# Stylophone.net
KiCad netlist of a schematic drawn in Altium Designer
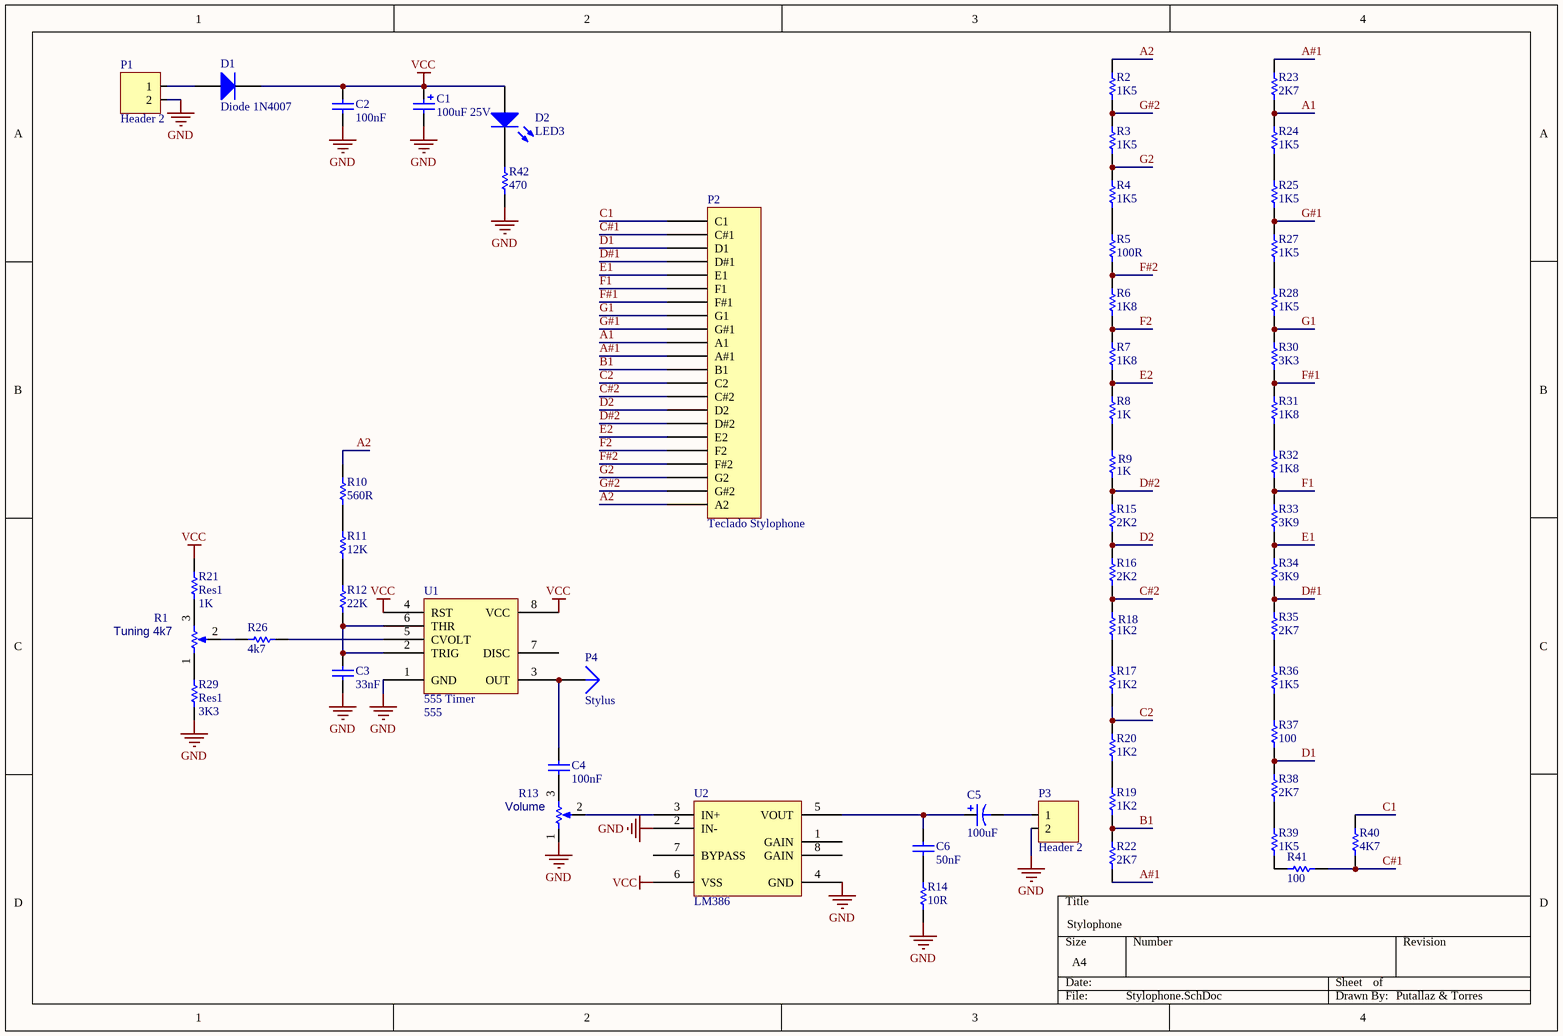
[diagram p0: Stylophone.SchDoc]

(export (version "E")
  (design (tool "Eeschema 10.0.6"))
  (components
    (comp (ref "C1")
      (value "100uF 25V")
      (footprint "CAP SMD 100uF 25V")
      (description "Polarized Capacitor (Radial)")
      (fields (field (name "PUBLISHER") "Altium Limited"))
      (libsource (lib "SchLibPutallaz") (part "Cap Pol1"))
    )
    (comp (ref "C2")
      (value "100nF")
      (footprint "0805 res-cap")
      (description "Capacitor")
      (fields (field (name "PUBLISHER") "Altium Limited"))
      (libsource (lib "SchLibPutallaz") (part "Cap"))
    )
    (comp (ref "C3")
      (value "33nF")
      (footprint "0805 res-cap")
      (description "Capacitor")
      (fields (field (name "PUBLISHER") "Altium Limited"))
      (libsource (lib "SchLibPutallaz") (part "Cap"))
    )
    (comp (ref "C4")
      (value "100nF")
      (footprint "0805 res-cap")
      (description "Capacitor")
      (fields (field (name "PUBLISHER") "Altium Limited"))
      (libsource (lib "SchLibPutallaz") (part "Cap"))
    )
    (comp (ref "C5")
      (value "100uF")
      (footprint "CAP SMD 100uF 25V")
      (description "Polarized Capacitor (Axial)")
      (fields (field (name "PUBLISHER") "Altium Limited"))
      (libsource (lib "SchLibPutallaz") (part "Cap Pol D16mm"))
    )
    (comp (ref "C6")
      (value "50nF")
      (footprint "0805 res-cap")
      (description "Capacitor")
      (fields (field (name "PUBLISHER") "Altium Limited"))
      (libsource (lib "SchLibPutallaz") (part "Cap"))
    )
    (comp (ref "D1")
      (value "Diode 1N4007")
      (footprint "DO214AC")
      (description "1 Amp General Purpose Rectifier")
      (fields (field (name "PUBLISHER") "Altium Limited"))
      (libsource (lib "SchLibPutallaz") (part "Diode 1N4007"))
    )
    (comp (ref "D2")
      (value "LED3")
      (footprint "1206 LED")
      (description "Typical BLUE SiC LED")
      (fields (field (name "PUBLISHER") "Altium Limited"))
      (libsource (lib "SchLibPutallaz") (part "LED3"))
    )
    (comp (ref "P1")
      (value "Header 2")
      (footprint "HDR1X2")
      (description "Header, 2-Pin")
      (fields (field (name "PUBLISHER") "Altium Limited"))
      (libsource (lib "") (part "Header 2_1"))
    )
    (comp (ref "P2")
      (value "Teclado Stylophone")
      (footprint "Teclado Stylophone")
      (libsource (lib "SchLibPutallaz") (part "Teclado Stylophone"))
    )
    (comp (ref "P3")
      (value "Header 2")
      (footprint "HDR1X2")
      (description "Header, 2-Pin")
      (fields (field (name "PUBLISHER") "Altium Limited"))
      (libsource (lib "SchLibPutallaz") (part "Header 2"))
    )
    (comp (ref "P4")
      (value "Stylus")
      (footprint "PIN1")
      (description "Plug")
      (fields (field (name "PUBLISHER") "Altium Limited"))
      (libsource (lib "Miscellaneous Connectors") (part "Plug"))
    )
    (comp (ref "R1")
      (value "Tuning 4k7")
      (footprint "TRIMMING POTENTIOMETER")
      (description "4K7")
      (libsource (lib "Simulation Generic Components") (part "Potentiometer"))
    )
    (comp (ref "R2")
      (value "1K5")
      (footprint "0805 res")
      (description "Resistor")
      (fields (field (name "PUBLISHER") "Altium Limited"))
      (libsource (lib "SchLibPutallaz") (part "Res1"))
    )
    (comp (ref "R3")
      (value "1K5")
      (footprint "0805 res")
      (description "Resistor")
      (fields (field (name "PUBLISHER") "Altium Limited"))
      (libsource (lib "SchLibPutallaz") (part "Res1"))
    )
    (comp (ref "R4")
      (value "1K5")
      (footprint "0805 res")
      (description "Resistor")
      (fields (field (name "PUBLISHER") "Altium Limited"))
      (libsource (lib "SchLibPutallaz") (part "Res1"))
    )
    (comp (ref "R5")
      (value "100R")
      (footprint "0805 res")
      (description "Resistor")
      (fields (field (name "PUBLISHER") "Altium Limited"))
      (libsource (lib "SchLibPutallaz") (part "Res1"))
    )
    (comp (ref "R6")
      (value "1K8")
      (footprint "0805 res")
      (description "Resistor")
      (fields (field (name "PUBLISHER") "Altium Limited"))
      (libsource (lib "SchLibPutallaz") (part "Res1"))
    )
    (comp (ref "R7")
      (value "1K8")
      (footprint "0805 res")
      (description "Resistor")
      (fields (field (name "PUBLISHER") "Altium Limited"))
      (libsource (lib "SchLibPutallaz") (part "Res1"))
    )
    (comp (ref "R8")
      (value "1K")
      (footprint "0805 res")
      (description "Resistor")
      (fields (field (name "PUBLISHER") "Altium Limited"))
      (libsource (lib "SchLibPutallaz") (part "Res1"))
    )
    (comp (ref "R9")
      (value "1K")
      (footprint "0805 res")
      (description "Resistor")
      (fields (field (name "PUBLISHER") "Altium Limited"))
      (libsource (lib "SchLibPutallaz") (part "Res1"))
    )
    (comp (ref "R10")
      (value "560R")
      (footprint "0805 res")
      (description "Resistor")
      (fields (field (name "PUBLISHER") "Altium Limited"))
      (libsource (lib "SchLibPutallaz") (part "Res1"))
    )
    (comp (ref "R11")
      (value "12K")
      (footprint "0805 res")
      (description "Resistor")
      (fields (field (name "PUBLISHER") "Altium Limited"))
      (libsource (lib "SchLibPutallaz") (part "Res1"))
    )
    (comp (ref "R12")
      (value "22K")
      (footprint "0805 res")
      (description "Resistor")
      (fields (field (name "PUBLISHER") "Altium Limited"))
      (libsource (lib "SchLibPutallaz") (part "Res1"))
    )
    (comp (ref "R13")
      (value "Volume")
      (footprint "TRIMMING POTENTIOMETER")
      (description "4K7")
      (libsource (lib "Simulation Generic Components") (part "Potentiometer"))
    )
    (comp (ref "R14")
      (value "10R")
      (footprint "0805 res")
      (description "Resistor")
      (fields (field (name "PUBLISHER") "Altium Limited"))
      (libsource (lib "SchLibPutallaz") (part "Res1"))
    )
    (comp (ref "R15")
      (value "2K2")
      (footprint "0805 res")
      (description "Resistor")
      (fields (field (name "PUBLISHER") "Altium Limited"))
      (libsource (lib "SchLibPutallaz") (part "Res1"))
    )
    (comp (ref "R16")
      (value "2K2")
      (footprint "0805 res")
      (description "Resistor")
      (fields (field (name "PUBLISHER") "Altium Limited"))
      (libsource (lib "SchLibPutallaz") (part "Res1"))
    )
    (comp (ref "R17")
      (value "1K2")
      (footprint "0805 res")
      (description "Resistor")
      (fields (field (name "PUBLISHER") "Altium Limited"))
      (libsource (lib "SchLibPutallaz") (part "Res1"))
    )
    (comp (ref "R18")
      (value "1K2")
      (footprint "0805 res")
      (description "Resistor")
      (fields (field (name "PUBLISHER") "Altium Limited"))
      (libsource (lib "SchLibPutallaz") (part "Res1"))
    )
    (comp (ref "R19")
      (value "1K2")
      (footprint "0805 res")
      (description "Resistor")
      (fields (field (name "PUBLISHER") "Altium Limited"))
      (libsource (lib "SchLibPutallaz") (part "Res1"))
    )
    (comp (ref "R20")
      (value "1K2")
      (footprint "0805 res")
      (description "Resistor")
      (fields (field (name "PUBLISHER") "Altium Limited"))
      (libsource (lib "SchLibPutallaz") (part "Res1"))
    )
    (comp (ref "R21")
      (value "Res1")
      (footprint "0805 res")
      (description "Resistor")
      (fields (field (name "ALTIUM_VALUE") "1K") (field (name "PUBLISHER") "Altium Limited"))
      (libsource (lib "SchLibPutallaz") (part "Res1"))
    )
    (comp (ref "R22")
      (value "2K7")
      (footprint "0805 res")
      (description "Resistor")
      (fields (field (name "PUBLISHER") "Altium Limited"))
      (libsource (lib "SchLibPutallaz") (part "Res1"))
    )
    (comp (ref "R23")
      (value "2K7")
      (footprint "0805 res")
      (description "Resistor")
      (fields (field (name "PUBLISHER") "Altium Limited"))
      (libsource (lib "SchLibPutallaz") (part "Res1"))
    )
    (comp (ref "R24")
      (value "1K5")
      (footprint "0805 res")
      (description "Resistor")
      (fields (field (name "PUBLISHER") "Altium Limited"))
      (libsource (lib "SchLibPutallaz") (part "Res1"))
    )
    (comp (ref "R25")
      (value "1K5")
      (footprint "0805 res")
      (description "Resistor")
      (fields (field (name "PUBLISHER") "Altium Limited"))
      (libsource (lib "SchLibPutallaz") (part "Res1"))
    )
    (comp (ref "R26")
      (value "4k7")
      (footprint "0805 res")
      (description "Resistor")
      (fields (field (name "PUBLISHER") "Altium Limited"))
      (libsource (lib "SchLibPutallaz") (part "Res1"))
    )
    (comp (ref "R27")
      (value "1K5")
      (footprint "0805 res")
      (description "Resistor")
      (fields (field (name "PUBLISHER") "Altium Limited"))
      (libsource (lib "SchLibPutallaz") (part "Res1"))
    )
    (comp (ref "R28")
      (value "1K5")
      (footprint "0805 res")
      (description "Resistor")
      (fields (field (name "PUBLISHER") "Altium Limited"))
      (libsource (lib "SchLibPutallaz") (part "Res1"))
    )
    (comp (ref "R29")
      (value "Res1")
      (footprint "0805 res")
      (description "Resistor")
      (fields (field (name "ALTIUM_VALUE") "3K3") (field (name "PUBLISHER") "Altium Limited"))
      (libsource (lib "SchLibPutallaz") (part "Res1"))
    )
    (comp (ref "R30")
      (value "3K3")
      (footprint "0805 res")
      (description "Resistor")
      (fields (field (name "PUBLISHER") "Altium Limited"))
      (libsource (lib "SchLibPutallaz") (part "Res1"))
    )
    (comp (ref "R31")
      (value "1K8")
      (footprint "0805 res")
      (description "Resistor")
      (fields (field (name "PUBLISHER") "Altium Limited"))
      (libsource (lib "SchLibPutallaz") (part "Res1"))
    )
    (comp (ref "R32")
      (value "1K8")
      (footprint "0805 res")
      (description "Resistor")
      (fields (field (name "PUBLISHER") "Altium Limited"))
      (libsource (lib "SchLibPutallaz") (part "Res1"))
    )
    (comp (ref "R33")
      (value "3K9")
      (footprint "0805 res")
      (description "Resistor")
      (fields (field (name "PUBLISHER") "Altium Limited"))
      (libsource (lib "SchLibPutallaz") (part "Res1"))
    )
    (comp (ref "R34")
      (value "3K9")
      (footprint "0805 res")
      (description "Resistor")
      (fields (field (name "PUBLISHER") "Altium Limited"))
      (libsource (lib "SchLibPutallaz") (part "Res1"))
    )
    (comp (ref "R35")
      (value "2K7")
      (footprint "0805 res")
      (description "Resistor")
      (fields (field (name "PUBLISHER") "Altium Limited"))
      (libsource (lib "SchLibPutallaz") (part "Res1"))
    )
    (comp (ref "R36")
      (value "1K5")
      (footprint "0805 res")
      (description "Resistor")
      (fields (field (name "PUBLISHER") "Altium Limited"))
      (libsource (lib "SchLibPutallaz") (part "Res1"))
    )
    (comp (ref "R37")
      (value "100")
      (footprint "0805 res")
      (description "Resistor")
      (fields (field (name "PUBLISHER") "Altium Limited"))
      (libsource (lib "SchLibPutallaz") (part "Res1"))
    )
    (comp (ref "R38")
      (value "2K7")
      (footprint "0805 res")
      (description "Resistor")
      (fields (field (name "PUBLISHER") "Altium Limited"))
      (libsource (lib "SchLibPutallaz") (part "Res1"))
    )
    (comp (ref "R39")
      (value "1K5")
      (footprint "0805 res")
      (description "Resistor")
      (fields (field (name "PUBLISHER") "Altium Limited"))
      (libsource (lib "SchLibPutallaz") (part "Res1"))
    )
    (comp (ref "R40")
      (value "4K7")
      (footprint "0805 res")
      (description "Resistor")
      (fields (field (name "PUBLISHER") "Altium Limited"))
      (libsource (lib "SchLibPutallaz") (part "Res1"))
    )
    (comp (ref "R41")
      (value "100")
      (footprint "0805 res")
      (description "Resistor")
      (fields (field (name "PUBLISHER") "Altium Limited"))
      (libsource (lib "SchLibPutallaz") (part "Res1"))
    )
    (comp (ref "R42")
      (value "470")
      (footprint "0805 res")
      (description "Resistor")
      (fields (field (name "PUBLISHER") "Altium Limited"))
      (libsource (lib "SchLibPutallaz") (part "Res1"))
    )
    (comp (ref "U1") (value "555") (footprint "SOIC-8") (libsource (lib "SchLibPutallaz") (part "555")))
    (comp (ref "U2") (value "LM386") (footprint "SOIC-8") (libsource (lib "SchLibPutallaz") (part "LM386")))
  )
  (nets
    (net (code "1") (name "/A#1") (class "Default")
      (node (ref "P2") (pin "A#1") (pinfunction "A#1_A#1") (pintype "passive"))
      (node (ref "R22") (pin "1") (pinfunction "1_1") (pintype "passive"))
      (node (ref "R23") (pin "2") (pinfunction "2_2") (pintype "passive"))
    )
    (net (code "2") (name "/A1") (class "Default")
      (node (ref "P2") (pin "A1") (pinfunction "A1_A1") (pintype "passive"))
      (node (ref "R23") (pin "1") (pinfunction "1_1") (pintype "passive"))
      (node (ref "R24") (pin "2") (pinfunction "2_2") (pintype "passive"))
    )
    (net (code "3") (name "/A2") (class "Default")
      (node (ref "P2") (pin "A2") (pinfunction "A2_A2") (pintype "passive"))
      (node (ref "R10") (pin "2") (pinfunction "2_2") (pintype "passive"))
      (node (ref "R2") (pin "2") (pinfunction "2_2") (pintype "passive"))
    )
    (net (code "4") (name "/B1") (class "Default")
      (node (ref "P2") (pin "B1") (pinfunction "B1_B1") (pintype "passive"))
      (node (ref "R19") (pin "2") (pinfunction "2_2") (pintype "passive"))
      (node (ref "R22") (pin "2") (pinfunction "2_2") (pintype "passive"))
    )
    (net (code "5") (name "/C#1") (class "Default")
      (node (ref "P2") (pin "C#1") (pinfunction "C#1_C#1") (pintype "passive"))
      (node (ref "R40") (pin "1") (pinfunction "1_1") (pintype "passive"))
      (node (ref "R41") (pin "1") (pinfunction "1_1") (pintype "passive"))
    )
    (net (code "6") (name "/C#2") (class "Default")
      (node (ref "P2") (pin "C#2") (pinfunction "C#2_C#2") (pintype "passive"))
      (node (ref "R16") (pin "1") (pinfunction "1_1") (pintype "passive"))
      (node (ref "R18") (pin "1") (pinfunction "1_1") (pintype "passive"))
    )
    (net (code "7") (name "/C1") (class "Default")
      (node (ref "P2") (pin "C1") (pinfunction "C1_C1") (pintype "passive"))
      (node (ref "R40") (pin "2") (pinfunction "2_2") (pintype "passive"))
    )
    (net (code "8") (name "/C2") (class "Default")
      (node (ref "P2") (pin "C2") (pinfunction "C2_C2") (pintype "passive"))
      (node (ref "R17") (pin "1") (pinfunction "1_1") (pintype "passive"))
      (node (ref "R20") (pin "1") (pinfunction "1_1") (pintype "passive"))
    )
    (net (code "9") (name "/D#1") (class "Default")
      (node (ref "P2") (pin "D#1") (pinfunction "D#1_D#1") (pintype "passive"))
      (node (ref "R34") (pin "1") (pinfunction "1_1") (pintype "passive"))
      (node (ref "R35") (pin "2") (pinfunction "2_2") (pintype "passive"))
    )
    (net (code "10") (name "/D#2") (class "Default")
      (node (ref "P2") (pin "D#2") (pinfunction "D#2_D#2") (pintype "passive"))
      (node (ref "R15") (pin "2") (pinfunction "2_2") (pintype "passive"))
      (node (ref "R9") (pin "1") (pinfunction "1_1") (pintype "passive"))
    )
    (net (code "11") (name "/D1") (class "Default")
      (node (ref "P2") (pin "D1") (pinfunction "D1_D1") (pintype "passive"))
      (node (ref "R37") (pin "1") (pinfunction "1_1") (pintype "passive"))
      (node (ref "R38") (pin "2") (pinfunction "2_2") (pintype "passive"))
    )
    (net (code "12") (name "/D2") (class "Default")
      (node (ref "P2") (pin "D2") (pinfunction "D2_D2") (pintype "passive"))
      (node (ref "R15") (pin "1") (pinfunction "1_1") (pintype "passive"))
      (node (ref "R16") (pin "2") (pinfunction "2_2") (pintype "passive"))
    )
    (net (code "13") (name "/E1") (class "Default")
      (node (ref "P2") (pin "E1") (pinfunction "E1_E1") (pintype "passive"))
      (node (ref "R33") (pin "1") (pinfunction "1_1") (pintype "passive"))
      (node (ref "R34") (pin "2") (pinfunction "2_2") (pintype "passive"))
    )
    (net (code "14") (name "/E2") (class "Default")
      (node (ref "P2") (pin "E2") (pinfunction "E2_E2") (pintype "passive"))
      (node (ref "R7") (pin "1") (pinfunction "1_1") (pintype "passive"))
      (node (ref "R8") (pin "1") (pinfunction "1_1") (pintype "passive"))
    )
    (net (code "15") (name "/F#1") (class "Default")
      (node (ref "P2") (pin "F#1") (pinfunction "F#1_F#1") (pintype "passive"))
      (node (ref "R30") (pin "1") (pinfunction "1_1") (pintype "passive"))
      (node (ref "R31") (pin "2") (pinfunction "2_2") (pintype "passive"))
    )
    (net (code "16") (name "/F#2") (class "Default")
      (node (ref "P2") (pin "F#2") (pinfunction "F#2_F#2") (pintype "passive"))
      (node (ref "R5") (pin "1") (pinfunction "1_1") (pintype "passive"))
      (node (ref "R6") (pin "2") (pinfunction "2_2") (pintype "passive"))
    )
    (net (code "17") (name "/F1") (class "Default")
      (node (ref "P2") (pin "F1") (pinfunction "F1_F1") (pintype "passive"))
      (node (ref "R32") (pin "1") (pinfunction "1_1") (pintype "passive"))
      (node (ref "R33") (pin "2") (pinfunction "2_2") (pintype "passive"))
    )
    (net (code "18") (name "/F2") (class "Default")
      (node (ref "P2") (pin "F2") (pinfunction "F2_F2") (pintype "passive"))
      (node (ref "R6") (pin "1") (pinfunction "1_1") (pintype "passive"))
      (node (ref "R7") (pin "2") (pinfunction "2_2") (pintype "passive"))
    )
    (net (code "19") (name "/G#1") (class "Default")
      (node (ref "P2") (pin "G#1") (pinfunction "G#1_G#1") (pintype "passive"))
      (node (ref "R25") (pin "1") (pinfunction "1_1") (pintype "passive"))
      (node (ref "R27") (pin "2") (pinfunction "2_2") (pintype "passive"))
    )
    (net (code "20") (name "/G#2") (class "Default")
      (node (ref "P2") (pin "G#2") (pinfunction "G#2_G#2") (pintype "passive"))
      (node (ref "R2") (pin "1") (pinfunction "1_1") (pintype "passive"))
      (node (ref "R3") (pin "2") (pinfunction "2_2") (pintype "passive"))
    )
    (net (code "21") (name "/G1") (class "Default")
      (node (ref "P2") (pin "G1") (pinfunction "G1_G1") (pintype "passive"))
      (node (ref "R28") (pin "1") (pinfunction "1_1") (pintype "passive"))
      (node (ref "R30") (pin "2") (pinfunction "2_2") (pintype "passive"))
    )
    (net (code "22") (name "/G2") (class "Default")
      (node (ref "P2") (pin "G2") (pinfunction "G2_G2") (pintype "passive"))
      (node (ref "R3") (pin "1") (pinfunction "1_1") (pintype "passive"))
      (node (ref "R4") (pin "2") (pinfunction "2_2") (pintype "passive"))
    )
    (net (code "23") (name "GND") (class "Default")
      (node (ref "C1") (pin "2") (pinfunction "2_2") (pintype "passive"))
      (node (ref "C2") (pin "1") (pinfunction "1_1") (pintype "passive"))
      (node (ref "C3") (pin "1") (pinfunction "1_1") (pintype "passive"))
      (node (ref "P1") (pin "2") (pinfunction "2_2") (pintype "passive"))
      (node (ref "P3") (pin "2") (pinfunction "2_2") (pintype "passive"))
      (node (ref "R13") (pin "1") (pinfunction "TOP_1") (pintype "passive"))
      (node (ref "R14") (pin "1") (pinfunction "1_1") (pintype "passive"))
      (node (ref "R29") (pin "1") (pinfunction "1_1") (pintype "passive"))
      (node (ref "R42") (pin "1") (pinfunction "1_1") (pintype "passive"))
      (node (ref "U1") (pin "1") (pinfunction "GND_1") (pintype "passive"))
      (node (ref "U2") (pin "2") (pinfunction "IN-_2") (pintype "passive"))
      (node (ref "U2") (pin "4") (pinfunction "GND_4") (pintype "passive"))
    )
    (net (code "24") (name "Net-(C5-Pad2)") (class "Default")
      (node (ref "C5") (pin "2") (pinfunction "2_2") (pintype "passive"))
      (node (ref "P3") (pin "1") (pinfunction "1_1") (pintype "passive"))
    )
    (net (code "25") (name "Net-(C6-Pad1)") (class "Default")
      (node (ref "C6") (pin "1") (pinfunction "1_1") (pintype "passive"))
      (node (ref "R14") (pin "2") (pinfunction "2_2") (pintype "passive"))
    )
    (net (code "26") (name "Net-(D1-A)") (class "Default")
      (node (ref "D1") (pin "1") (pinfunction "A_1") (pintype "passive"))
      (node (ref "P1") (pin "1") (pinfunction "1_1") (pintype "passive"))
    )
    (net (code "27") (name "Net-(D2-K)") (class "Default")
      (node (ref "D2") (pin "2") (pinfunction "K_2") (pintype "passive"))
      (node (ref "R42") (pin "2") (pinfunction "2_2") (pintype "passive"))
    )
    (net (code "28") (name "Net-(R1-BOT)") (class "Default")
      (node (ref "R1") (pin "3") (pinfunction "BOT_3") (pintype "passive"))
      (node (ref "R21") (pin "1") (pinfunction "1_1") (pintype "passive"))
    )
    (net (code "29") (name "Net-(R1-TAP)") (class "Default")
      (node (ref "R1") (pin "2") (pinfunction "TAP_2") (pintype "passive"))
      (node (ref "R26") (pin "1") (pinfunction "1_1") (pintype "passive"))
    )
    (net (code "30") (name "Net-(R1-TOP)") (class "Default")
      (node (ref "R1") (pin "1") (pinfunction "TOP_1") (pintype "passive"))
      (node (ref "R29") (pin "2") (pinfunction "2_2") (pintype "passive"))
    )
    (net (code "31") (name "Net-(R4-Pad1)") (class "Default")
      (node (ref "R4") (pin "1") (pinfunction "1_1") (pintype "passive"))
      (node (ref "R5") (pin "2") (pinfunction "2_2") (pintype "passive"))
    )
    (net (code "32") (name "Net-(R8-Pad2)") (class "Default")
      (node (ref "R8") (pin "2") (pinfunction "2_2") (pintype "passive"))
      (node (ref "R9") (pin "2") (pinfunction "2_2") (pintype "passive"))
    )
    (net (code "33") (name "Net-(R10-Pad1)") (class "Default")
      (node (ref "R10") (pin "1") (pinfunction "1_1") (pintype "passive"))
      (node (ref "R11") (pin "2") (pinfunction "2_2") (pintype "passive"))
    )
    (net (code "34") (name "Net-(R11-Pad1)") (class "Default")
      (node (ref "R11") (pin "1") (pinfunction "1_1") (pintype "passive"))
      (node (ref "R12") (pin "2") (pinfunction "2_2") (pintype "passive"))
    )
    (net (code "35") (name "Net-(R13-BOT)") (class "Default")
      (node (ref "C4") (pin "2") (pinfunction "2_2") (pintype "passive"))
      (node (ref "R13") (pin "3") (pinfunction "BOT_3") (pintype "passive"))
    )
    (net (code "36") (name "Net-(R13-TAP)") (class "Default")
      (node (ref "R13") (pin "2") (pinfunction "TAP_2") (pintype "passive"))
      (node (ref "U2") (pin "3") (pinfunction "IN+_3") (pintype "passive"))
    )
    (net (code "37") (name "Net-(R17-Pad2)") (class "Default")
      (node (ref "R17") (pin "2") (pinfunction "2_2") (pintype "passive"))
      (node (ref "R18") (pin "2") (pinfunction "2_2") (pintype "passive"))
    )
    (net (code "38") (name "Net-(R19-Pad1)") (class "Default")
      (node (ref "R19") (pin "1") (pinfunction "1_1") (pintype "passive"))
      (node (ref "R20") (pin "2") (pinfunction "2_2") (pintype "passive"))
    )
    (net (code "39") (name "Net-(R24-Pad1)") (class "Default")
      (node (ref "R24") (pin "1") (pinfunction "1_1") (pintype "passive"))
      (node (ref "R25") (pin "2") (pinfunction "2_2") (pintype "passive"))
    )
    (net (code "40") (name "Net-(R27-Pad1)") (class "Default")
      (node (ref "R27") (pin "1") (pinfunction "1_1") (pintype "passive"))
      (node (ref "R28") (pin "2") (pinfunction "2_2") (pintype "passive"))
    )
    (net (code "41") (name "Net-(R31-Pad1)") (class "Default")
      (node (ref "R31") (pin "1") (pinfunction "1_1") (pintype "passive"))
      (node (ref "R32") (pin "2") (pinfunction "2_2") (pintype "passive"))
    )
    (net (code "42") (name "Net-(R35-Pad1)") (class "Default")
      (node (ref "R35") (pin "1") (pinfunction "1_1") (pintype "passive"))
      (node (ref "R36") (pin "2") (pinfunction "2_2") (pintype "passive"))
    )
    (net (code "43") (name "Net-(R36-Pad1)") (class "Default")
      (node (ref "R36") (pin "1") (pinfunction "1_1") (pintype "passive"))
      (node (ref "R37") (pin "2") (pinfunction "2_2") (pintype "passive"))
    )
    (net (code "44") (name "Net-(R38-Pad1)") (class "Default")
      (node (ref "R38") (pin "1") (pinfunction "1_1") (pintype "passive"))
      (node (ref "R39") (pin "2") (pinfunction "2_2") (pintype "passive"))
    )
    (net (code "45") (name "Net-(R39-Pad1)") (class "Default")
      (node (ref "R39") (pin "1") (pinfunction "1_1") (pintype "passive"))
      (node (ref "R41") (pin "2") (pinfunction "2_2") (pintype "passive"))
    )
    (net (code "46") (name "Net-(U1-CVOLT)") (class "Default")
      (node (ref "R26") (pin "2") (pinfunction "2_2") (pintype "passive"))
      (node (ref "U1") (pin "5") (pinfunction "CVOLT_5") (pintype "passive"))
    )
    (net (code "47") (name "Net-(U1-OUT)") (class "Default")
      (node (ref "C4") (pin "1") (pinfunction "1_1") (pintype "passive"))
      (node (ref "P4") (pin "1") (pinfunction "1_1") (pintype "passive"))
      (node (ref "U1") (pin "3") (pinfunction "OUT_3") (pintype "passive"))
    )
    (net (code "48") (name "Net-(U1-THR)") (class "Default")
      (node (ref "C3") (pin "2") (pinfunction "2_2") (pintype "passive"))
      (node (ref "R12") (pin "1") (pinfunction "1_1") (pintype "passive"))
      (node (ref "U1") (pin "2") (pinfunction "TRIG_2") (pintype "passive"))
      (node (ref "U1") (pin "6") (pinfunction "THR_6") (pintype "passive"))
    )
    (net (code "49") (name "Net-(U2-VOUT)") (class "Default")
      (node (ref "C5") (pin "1") (pinfunction "1_1") (pintype "passive"))
      (node (ref "C6") (pin "2") (pinfunction "2_2") (pintype "passive"))
      (node (ref "U2") (pin "5") (pinfunction "VOUT_5") (pintype "passive"))
    )
    (net (code "50") (name "VCC") (class "Default")
      (node (ref "C1") (pin "1") (pinfunction "1_1") (pintype "passive"))
      (node (ref "C2") (pin "2") (pinfunction "2_2") (pintype "passive"))
      (node (ref "D1") (pin "2") (pinfunction "K_2") (pintype "passive"))
      (node (ref "D2") (pin "1") (pinfunction "A_1") (pintype "passive"))
      (node (ref "R21") (pin "2") (pinfunction "2_2") (pintype "passive"))
      (node (ref "U1") (pin "4") (pinfunction "RST_4") (pintype "passive"))
      (node (ref "U1") (pin "8") (pinfunction "VCC_8") (pintype "passive"))
      (node (ref "U2") (pin "6") (pinfunction "VSS_6") (pintype "passive"))
    )
    (net (code "51") (name "unconnected-(U1-DISC-Pad7)") (class "Default")
      (node (ref "U1") (pin "7") (pinfunction "DISC_7") (pintype "passive"))
    )
    (net (code "52") (name "unconnected-(U2-BYPASS-Pad7)") (class "Default")
      (node (ref "U2") (pin "7") (pinfunction "BYPASS_7") (pintype "passive"))
    )
    (net (code "53") (name "unconnected-(U2-GAIN-Pad1)") (class "Default")
      (node (ref "U2") (pin "1") (pinfunction "GAIN_1") (pintype "passive"))
    )
    (net (code "54") (name "unconnected-(U2-GAIN-Pad8)") (class "Default")
      (node (ref "U2") (pin "8") (pinfunction "GAIN_8") (pintype "passive"))
    )
  )
)
